# POWER_Amplifier.net
KiCad netlist of a schematic drawn in Altium Designer
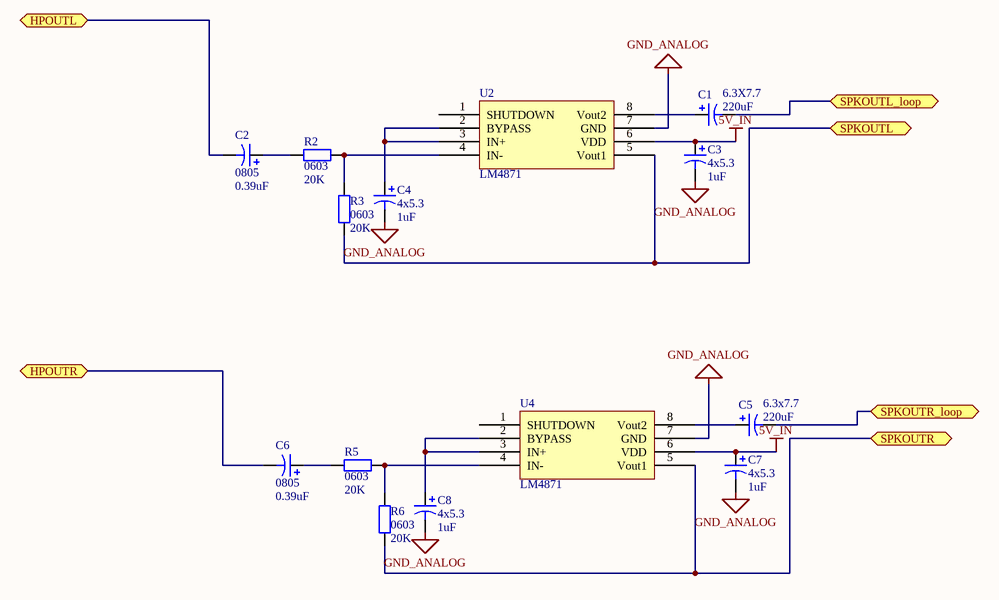
[diagram p0: POWER Amplifier.SchDoc]

(export (version "E")
  (design (tool "Eeschema 10.0.6"))
  (components
    (comp (ref "C1")
      (value "6.3X7.7")
      (footprint "SMD Electrolytic Capacitors 6.3 X 7.7")
      (description "Polarized Capacitor (Radial)")
      (fields (field (name "ALTIUM_VALUE") "220uF") (field (name "PUBLISHER") "Altium Limited"))
      (libsource (lib "Miscellaneous Devices") (part "Cap Pol1"))
    )
    (comp (ref "C2")
      (value "0805")
      (footprint "0805")
      (description "Polarized Capacitor (Radial)")
      (fields (field (name "ALTIUM_VALUE") "0.39uF") (field (name "PUBLISHER") "Altium Limited"))
      (libsource (lib "Miscellaneous Devices") (part "Cap Pol1"))
    )
    (comp (ref "C3")
      (value "4x5.3")
      (footprint "SMD Electrolytic Capacitors 4X 5.3")
      (description "Polarized Capacitor (Radial)")
      (fields (field (name "ALTIUM_VALUE") "1uF") (field (name "PUBLISHER") "Altium Limited"))
      (libsource (lib "Miscellaneous Devices") (part "Cap Pol1"))
    )
    (comp (ref "C4")
      (value "4x5.3")
      (footprint "SMD Electrolytic Capacitors 4X 5.3")
      (description "Polarized Capacitor (Radial)")
      (fields (field (name "ALTIUM_VALUE") "1uF") (field (name "PUBLISHER") "Altium Limited"))
      (libsource (lib "Miscellaneous Devices") (part "Cap Pol1"))
    )
    (comp (ref "C5")
      (value "6.3x7.7")
      (footprint "SMD Electrolytic Capacitors 6.3 X 7.7")
      (description "Polarized Capacitor (Radial)")
      (fields (field (name "ALTIUM_VALUE") "220uF") (field (name "PUBLISHER") "Altium Limited"))
      (libsource (lib "Miscellaneous Devices") (part "Cap Pol1"))
    )
    (comp (ref "C6")
      (value "0805")
      (footprint "0805")
      (description "Polarized Capacitor (Radial)")
      (fields (field (name "ALTIUM_VALUE") "0.39uF") (field (name "PUBLISHER") "Altium Limited"))
      (libsource (lib "Miscellaneous Devices") (part "Cap Pol1"))
    )
    (comp (ref "C7")
      (value "4x5.3")
      (footprint "SMD Electrolytic Capacitors 4X 5.3")
      (description "Polarized Capacitor (Radial)")
      (fields (field (name "ALTIUM_VALUE") "1uF") (field (name "PUBLISHER") "Altium Limited"))
      (libsource (lib "Miscellaneous Devices") (part "Cap Pol1"))
    )
    (comp (ref "C8")
      (value "4x5.3")
      (footprint "SMD Electrolytic Capacitors 4X 5.3")
      (description "Polarized Capacitor (Radial)")
      (fields (field (name "ALTIUM_VALUE") "1uF") (field (name "PUBLISHER") "Altium Limited"))
      (libsource (lib "Miscellaneous Devices") (part "Cap Pol1"))
    )
    (comp (ref "R2")
      (value "0603")
      (footprint "0603")
      (description "Resistor")
      (fields (field (name "ALTIUM_VALUE") "20K") (field (name "PUBLISHER") "Altium Limited"))
      (libsource (lib "Miscellaneous Devices") (part "Res2"))
    )
    (comp (ref "R3")
      (value "0603")
      (footprint "0603")
      (description "Resistor")
      (fields (field (name "ALTIUM_VALUE") "20K") (field (name "PUBLISHER") "Altium Limited"))
      (libsource (lib "") (part "Res2_1"))
    )
    (comp (ref "R5")
      (value "0603")
      (footprint "0603")
      (description "Resistor")
      (fields (field (name "ALTIUM_VALUE") "20K") (field (name "PUBLISHER") "Altium Limited"))
      (libsource (lib "Miscellaneous Devices") (part "Res2"))
    )
    (comp (ref "R6")
      (value "0603")
      (footprint "0603")
      (description "Resistor")
      (fields (field (name "ALTIUM_VALUE") "20K") (field (name "PUBLISHER") "Altium Limited"))
      (libsource (lib "") (part "Res2_1"))
    )
    (comp (ref "U2") (value "LM4871") (footprint "LM4871M-SOP8") (libsource (lib "IMX6DL") (part "LM4871")))
    (comp (ref "U4") (value "LM4871") (footprint "LM4871M-SOP8") (libsource (lib "IMX6DL") (part "LM4871")))
  )
  (nets
    (net (code "1") (name "/HPOUTL") (class "Default")
      (node (ref "C2") (pin "2") (pinfunction "2_2") (pintype "passive"))
    )
    (net (code "2") (name "/HPOUTR") (class "Default")
      (node (ref "C6") (pin "2") (pinfunction "2_2") (pintype "passive"))
    )
    (net (code "3") (name "/SPKOUTL") (class "Default")
      (node (ref "R3") (pin "2") (pinfunction "2_2") (pintype "passive"))
      (node (ref "U2") (pin "5") (pinfunction "Vout1_5") (pintype "passive"))
    )
    (net (code "4") (name "/SPKOUTL_loop") (class "Default")
      (node (ref "C1") (pin "2") (pinfunction "2_2") (pintype "passive"))
    )
    (net (code "5") (name "/SPKOUTR") (class "Default")
      (node (ref "R6") (pin "2") (pinfunction "2_2") (pintype "passive"))
      (node (ref "U4") (pin "5") (pinfunction "Vout1_5") (pintype "passive"))
    )
    (net (code "6") (name "/SPKOUTR_loop") (class "Default")
      (node (ref "C5") (pin "2") (pinfunction "2_2") (pintype "passive"))
    )
    (net (code "7") (name "5V_IN") (class "Default")
      (node (ref "C3") (pin "1") (pinfunction "1_1") (pintype "passive"))
      (node (ref "C7") (pin "1") (pinfunction "1_1") (pintype "passive"))
      (node (ref "U2") (pin "6") (pinfunction "VDD_6") (pintype "passive"))
      (node (ref "U4") (pin "6") (pinfunction "VDD_6") (pintype "passive"))
    )
    (net (code "8") (name "GND_ANALOG") (class "Default")
      (node (ref "C3") (pin "2") (pinfunction "2_2") (pintype "passive"))
      (node (ref "C4") (pin "2") (pinfunction "2_2") (pintype "passive"))
      (node (ref "C7") (pin "2") (pinfunction "2_2") (pintype "passive"))
      (node (ref "C8") (pin "2") (pinfunction "2_2") (pintype "passive"))
      (node (ref "U2") (pin "7") (pinfunction "GND_7") (pintype "passive"))
      (node (ref "U4") (pin "7") (pinfunction "GND_7") (pintype "passive"))
    )
    (net (code "9") (name "Net-(C2-Pad1)") (class "Default")
      (node (ref "C2") (pin "1") (pinfunction "1_1") (pintype "passive"))
      (node (ref "R2") (pin "2") (pinfunction "2_2") (pintype "passive"))
    )
    (net (code "10") (name "Net-(C6-Pad1)") (class "Default")
      (node (ref "C6") (pin "1") (pinfunction "1_1") (pintype "passive"))
      (node (ref "R5") (pin "2") (pinfunction "2_2") (pintype "passive"))
    )
    (net (code "11") (name "Net-(U2-BYPASS)") (class "Default")
      (node (ref "C4") (pin "1") (pinfunction "1_1") (pintype "passive"))
      (node (ref "U2") (pin "2") (pinfunction "BYPASS_2") (pintype "passive"))
      (node (ref "U2") (pin "3") (pinfunction "IN+_3") (pintype "passive"))
    )
    (net (code "12") (name "Net-(U2-IN-)") (class "Default")
      (node (ref "R2") (pin "1") (pinfunction "1_1") (pintype "passive"))
      (node (ref "R3") (pin "1") (pinfunction "1_1") (pintype "passive"))
      (node (ref "U2") (pin "4") (pinfunction "IN-_4") (pintype "passive"))
    )
    (net (code "13") (name "Net-(U2-Vout2)") (class "Default")
      (node (ref "C1") (pin "1") (pinfunction "1_1") (pintype "passive"))
      (node (ref "U2") (pin "8") (pinfunction "Vout2_8") (pintype "passive"))
    )
    (net (code "14") (name "Net-(U4-BYPASS)") (class "Default")
      (node (ref "C8") (pin "1") (pinfunction "1_1") (pintype "passive"))
      (node (ref "U4") (pin "2") (pinfunction "BYPASS_2") (pintype "passive"))
      (node (ref "U4") (pin "3") (pinfunction "IN+_3") (pintype "passive"))
    )
    (net (code "15") (name "Net-(U4-IN-)") (class "Default")
      (node (ref "R5") (pin "1") (pinfunction "1_1") (pintype "passive"))
      (node (ref "R6") (pin "1") (pinfunction "1_1") (pintype "passive"))
      (node (ref "U4") (pin "4") (pinfunction "IN-_4") (pintype "passive"))
    )
    (net (code "16") (name "Net-(U4-Vout2)") (class "Default")
      (node (ref "C5") (pin "1") (pinfunction "1_1") (pintype "passive"))
      (node (ref "U4") (pin "8") (pinfunction "Vout2_8") (pintype "passive"))
    )
    (net (code "17") (name "unconnected-(U2-SHUTDOWN-Pad1)") (class "Default")
      (node (ref "U2") (pin "1") (pinfunction "SHUTDOWN_1") (pintype "passive"))
    )
    (net (code "18") (name "unconnected-(U4-SHUTDOWN-Pad1)") (class "Default")
      (node (ref "U4") (pin "1") (pinfunction "SHUTDOWN_1") (pintype "passive"))
    )
  )
)
